# max21100_v2.net
KiCad netlist of a schematic drawn in EAGLE
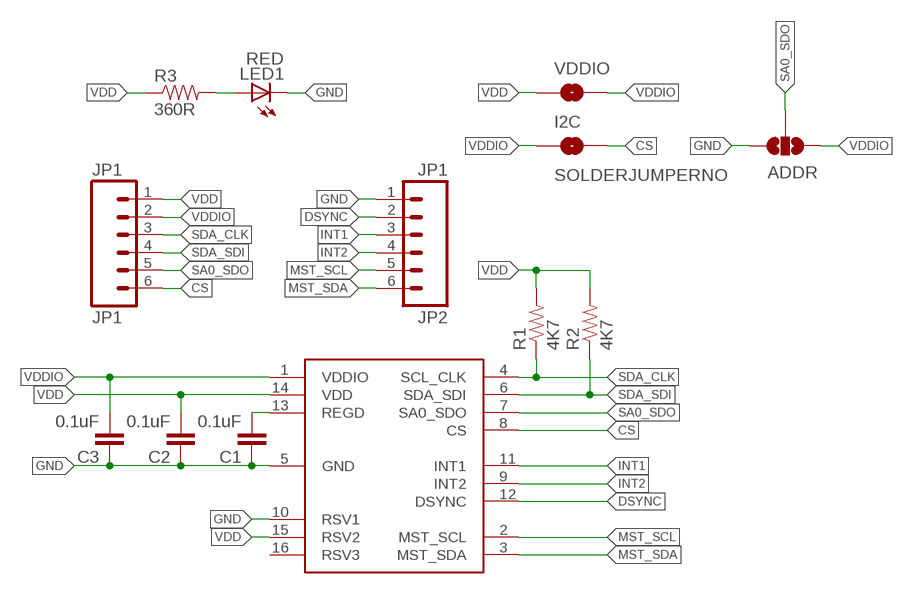
[diagram p0: schematic, sheet 1]

(export (version "E")
  (design (tool "Eeschema 10.0.6"))
  (components
    (comp (ref "ADDR")
      (value "SOLDERJUMPER_2WAYS")
      (footprint "eagle-import:SJ_3")
      (libsource (lib "eagle-import") (part "SOLDERJUMPER_2WAYS"))
    )
    (comp (ref "C1")
      (value "0.1uF")
      (footprint "eagle-import:0603-CAP")
      (libsource (lib "eagle-import") (part "CAP0603-CAP"))
    )
    (comp (ref "C2")
      (value "0.1uF")
      (footprint "eagle-import:0603-CAP")
      (libsource (lib "eagle-import") (part "CAP0603-CAP"))
    )
    (comp (ref "C3")
      (value "0.1uF")
      (footprint "eagle-import:0603-CAP")
      (libsource (lib "eagle-import") (part "CAP0603-CAP"))
    )
    (comp (ref "I2C")
      (value "SOLDERJUMPERNO")
      (footprint "eagle-import:SJ_2S-NO")
      (libsource (lib "eagle-import") (part "SOLDERJUMPERNO"))
    )
    (comp (ref "JP1")
      (value "JP1")
      (footprint "eagle-import:1X06")
      (libsource (lib "eagle-import") (part "M06SIP"))
    )
    (comp (ref "JP2")
      (value "JP1")
      (footprint "eagle-import:1X06")
      (libsource (lib "eagle-import") (part "M06SIP"))
    )
    (comp (ref "LED1")
      (value "RED")
      (footprint "eagle-import:CHIP-LED0603")
      (libsource (lib "eagle-import") (part "LEDCHIP-LED0603"))
    )
    (comp (ref "R1")
      (value "4K7")
      (footprint "eagle-import:0603-RES")
      (libsource (lib "eagle-import") (part "RESISTOR0603-RES"))
    )
    (comp (ref "R2")
      (value "4K7")
      (footprint "eagle-import:0603-RES")
      (libsource (lib "eagle-import") (part "RESISTOR0603-RES"))
    )
    (comp (ref "R3")
      (value "360R")
      (footprint "eagle-import:0603-RES")
      (libsource (lib "eagle-import") (part "RESISTOR0603-RES"))
    )
    (comp (ref "U$1")
      (value "MAX21100")
      (footprint "eagle-import:MAX21100")
      (libsource (lib "eagle-import") (part "MAX21100"))
    )
    (comp (ref "VDDIO")
      (value "SOLDERJUMPERTRACE")
      (footprint "eagle-import:SJ_2S-TRACE")
      (libsource (lib "eagle-import") (part "SOLDERJUMPERTRACE"))
    )
  )
  (nets
    (net (code "1") (name "CS") (class "Default")
      (node (ref "I2C") (pin "2") (pinfunction "2_2") (pintype "passive"))
      (node (ref "JP1") (pin "6") (pinfunction "6_6") (pintype "passive"))
      (node (ref "U$1") (pin "8") (pinfunction "CS_8") (pintype "bidirectional"))
    )
    (net (code "2") (name "DSYNC") (class "Default")
      (node (ref "JP2") (pin "2") (pinfunction "2_2") (pintype "passive"))
      (node (ref "U$1") (pin "12") (pinfunction "DSYNC_12") (pintype "bidirectional"))
    )
    (net (code "3") (name "GND") (class "Default")
      (node (ref "ADDR") (pin "1") (pinfunction "1_1") (pintype "passive"))
      (node (ref "C1") (pin "1") (pinfunction "1_1") (pintype "passive"))
      (node (ref "C2") (pin "1") (pinfunction "1_1") (pintype "passive"))
      (node (ref "C3") (pin "1") (pinfunction "1_1") (pintype "passive"))
      (node (ref "JP2") (pin "1") (pinfunction "1_1") (pintype "passive"))
      (node (ref "LED1") (pin "C") (pinfunction "C_C") (pintype "passive"))
      (node (ref "U$1") (pin "10") (pinfunction "RSV1_10") (pintype "bidirectional"))
      (node (ref "U$1") (pin "5") (pinfunction "GND_5") (pintype "bidirectional"))
    )
    (net (code "4") (name "INT1") (class "Default")
      (node (ref "JP2") (pin "3") (pinfunction "3_3") (pintype "passive"))
      (node (ref "U$1") (pin "11") (pinfunction "INT1_11") (pintype "bidirectional"))
    )
    (net (code "5") (name "INT2") (class "Default")
      (node (ref "JP2") (pin "4") (pinfunction "4_4") (pintype "passive"))
      (node (ref "U$1") (pin "9") (pinfunction "INT2_9") (pintype "bidirectional"))
    )
    (net (code "6") (name "MST_SCL") (class "Default")
      (node (ref "JP2") (pin "5") (pinfunction "5_5") (pintype "passive"))
      (node (ref "U$1") (pin "2") (pinfunction "MST_SCL_2") (pintype "bidirectional"))
    )
    (net (code "7") (name "MST_SDA") (class "Default")
      (node (ref "JP2") (pin "6") (pinfunction "6_6") (pintype "passive"))
      (node (ref "U$1") (pin "3") (pinfunction "MST_SDA_3") (pintype "bidirectional"))
    )
    (net (code "8") (name "Net-(LED1-PadA)") (class "Default")
      (node (ref "LED1") (pin "A") (pinfunction "A_A") (pintype "passive"))
      (node (ref "R3") (pin "2") (pinfunction "2_2") (pintype "passive"))
    )
    (net (code "9") (name "Net-(U$1-REGD)") (class "Default")
      (node (ref "C1") (pin "2") (pinfunction "2_2") (pintype "passive"))
      (node (ref "U$1") (pin "13") (pinfunction "REGD_13") (pintype "bidirectional"))
    )
    (net (code "10") (name "SA0_SDO") (class "Default")
      (node (ref "ADDR") (pin "2") (pinfunction "2_2") (pintype "passive"))
      (node (ref "JP1") (pin "5") (pinfunction "5_5") (pintype "passive"))
      (node (ref "U$1") (pin "7") (pinfunction "SA0_SDO_7") (pintype "bidirectional"))
    )
    (net (code "11") (name "SDA_CLK") (class "Default")
      (node (ref "JP1") (pin "3") (pinfunction "3_3") (pintype "passive"))
      (node (ref "R1") (pin "1") (pinfunction "1_1") (pintype "passive"))
      (node (ref "U$1") (pin "4") (pinfunction "SCL_CLK_4") (pintype "bidirectional"))
    )
    (net (code "12") (name "SDA_SDI") (class "Default")
      (node (ref "JP1") (pin "4") (pinfunction "4_4") (pintype "passive"))
      (node (ref "R2") (pin "1") (pinfunction "1_1") (pintype "passive"))
      (node (ref "U$1") (pin "6") (pinfunction "SDA_SDI_6") (pintype "bidirectional"))
    )
    (net (code "13") (name "VDD") (class "Default")
      (node (ref "C2") (pin "2") (pinfunction "2_2") (pintype "passive"))
      (node (ref "JP1") (pin "1") (pinfunction "1_1") (pintype "passive"))
      (node (ref "R1") (pin "2") (pinfunction "2_2") (pintype "passive"))
      (node (ref "R2") (pin "2") (pinfunction "2_2") (pintype "passive"))
      (node (ref "R3") (pin "1") (pinfunction "1_1") (pintype "passive"))
      (node (ref "U$1") (pin "14") (pinfunction "VDD_14") (pintype "bidirectional"))
      (node (ref "U$1") (pin "15") (pinfunction "RSV2_15") (pintype "bidirectional"))
      (node (ref "VDDIO") (pin "1") (pinfunction "1_1") (pintype "passive"))
    )
    (net (code "14") (name "VDDIO") (class "Default")
      (node (ref "ADDR") (pin "3") (pinfunction "3_3") (pintype "passive"))
      (node (ref "C3") (pin "2") (pinfunction "2_2") (pintype "passive"))
      (node (ref "I2C") (pin "1") (pinfunction "1_1") (pintype "passive"))
      (node (ref "JP1") (pin "2") (pinfunction "2_2") (pintype "passive"))
      (node (ref "U$1") (pin "1") (pinfunction "VDDIO_1") (pintype "bidirectional"))
      (node (ref "VDDIO") (pin "2") (pinfunction "2_2") (pintype "passive"))
    )
    (net (code "15") (name "unconnected-(U$1-RSV3-Pad16)") (class "Default")
      (node (ref "U$1") (pin "16") (pinfunction "RSV3_16") (pintype "bidirectional"))
    )
  )
)
